# ROM-Adapter5.net
KiCad netlist of a schematic drawn in EAGLE
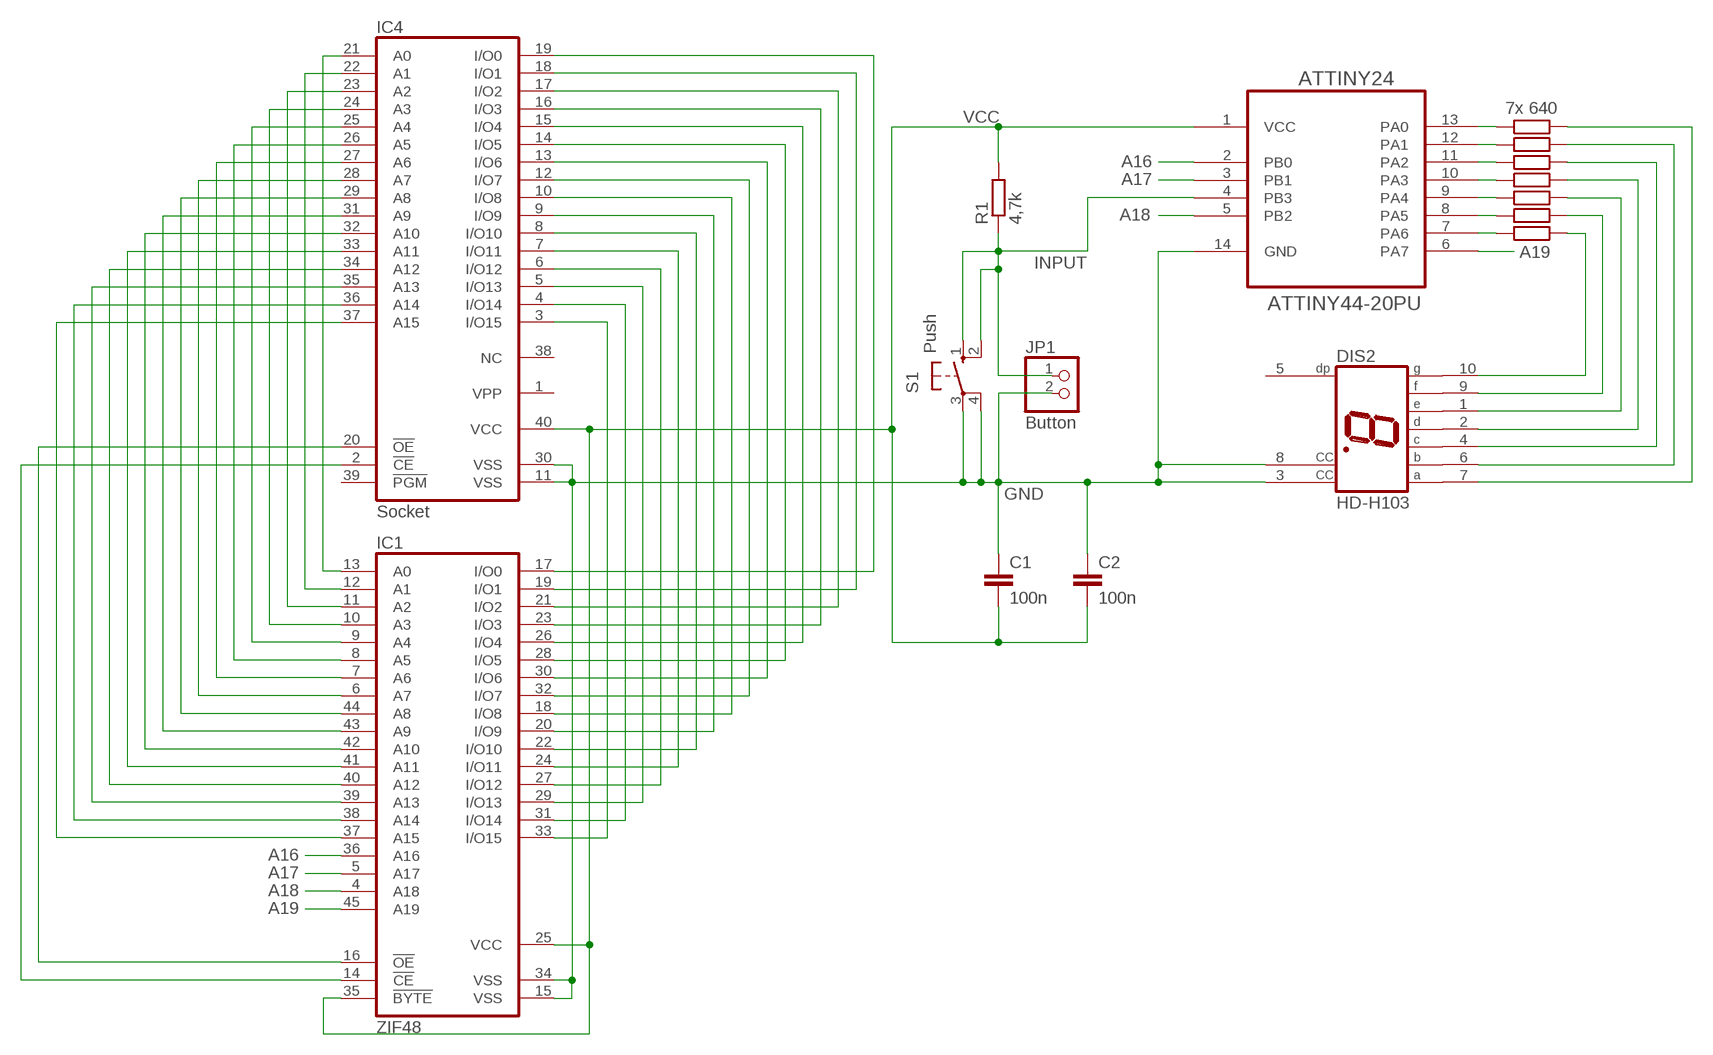
[diagram p0: schematic, sheet 1]

(export (version "E")
  (design (tool "Eeschema 10.0.6"))
  (components
    (comp (ref "ATTINY24")
      (value "ATTINY44-20PU")
      (footprint "eagle-import:DIP254P762X533-14")
      (libsource (lib "eagle-import") (part "ATTINY44-20PU"))
    )
    (comp (ref "C1")
      (value "100n")
      (footprint "eagle-import:C025-030X050")
      (libsource (lib "eagle-import") (part "C-EU025-030X050"))
    )
    (comp (ref "C2")
      (value "100n")
      (footprint "eagle-import:C025-030X050")
      (libsource (lib "eagle-import") (part "C-EU025-030X050"))
    )
    (comp (ref "DIS2")
      (value "HD-H103")
      (footprint "eagle-import:HDSP-M")
      (libsource (lib "eagle-import") (part "HD-H103"))
    )
    (comp (ref "IC1")
      (value "ZIF48")
      (footprint "eagle-import:MEMORY-HITACHI_ZIF48")
      (libsource (lib "eagle-import") (part "MEMORY-M27C160"))
    )
    (comp (ref "IC4")
      (value "Socket")
      (footprint "eagle-import:DIL40")
      (libsource (lib "eagle-import") (part "27C1024HG"))
    )
    (comp (ref "JP1")
      (value "Button")
      (footprint "eagle-import:1X02")
      (libsource (lib "eagle-import") (part "PINHD-1X2"))
    )
    (comp (ref "R1")
      (value "4,7k")
      (footprint "eagle-import:0207_10")
      (libsource (lib "eagle-import") (part "R-EU_0207/10"))
    )
    (comp (ref "R2")
      (value "7x 640")
      (footprint "eagle-import:0207_10")
      (libsource (lib "eagle-import") (part "R-EU_0207/10"))
    )
    (comp (ref "R3")
      (value "640")
      (footprint "eagle-import:0207_10")
      (libsource (lib "eagle-import") (part "R-EU_0207/10"))
    )
    (comp (ref "R4")
      (value "640")
      (footprint "eagle-import:0207_10")
      (libsource (lib "eagle-import") (part "R-EU_0207/10"))
    )
    (comp (ref "R5")
      (value "640")
      (footprint "eagle-import:0207_10")
      (libsource (lib "eagle-import") (part "R-EU_0207/10"))
    )
    (comp (ref "R6")
      (value "640")
      (footprint "eagle-import:0207_10")
      (libsource (lib "eagle-import") (part "R-EU_0207/10"))
    )
    (comp (ref "R7")
      (value "640")
      (footprint "eagle-import:0207_10")
      (libsource (lib "eagle-import") (part "R-EU_0207/10"))
    )
    (comp (ref "R8")
      (value "640")
      (footprint "eagle-import:0207_10")
      (libsource (lib "eagle-import") (part "R-EU_0207/10"))
    )
    (comp (ref "S1")
      (value "Push")
      (footprint "eagle-import:B3F-10XX")
      (fields (field (name "MPN") "B3F-1000"))
      (libsource (lib "eagle-import") (part "10-XX"))
    )
  )
  (nets
    (net (code "1") (name "/A16") (class "Default")
      (node (ref "ATTINY24") (pin "2") (pinfunction "PB0_2") (pintype "bidirectional"))
      (node (ref "IC1") (pin "36") (pinfunction "A16_36") (pintype "input"))
    )
    (net (code "2") (name "/A17") (class "Default")
      (node (ref "ATTINY24") (pin "3") (pinfunction "PB1_3") (pintype "bidirectional"))
      (node (ref "IC1") (pin "5") (pinfunction "A17_5") (pintype "input"))
    )
    (net (code "3") (name "/A18") (class "Default")
      (node (ref "ATTINY24") (pin "5") (pinfunction "PB2_5") (pintype "bidirectional"))
      (node (ref "IC1") (pin "4") (pinfunction "A18_4") (pintype "input"))
    )
    (net (code "4") (name "/A19") (class "Default")
      (node (ref "ATTINY24") (pin "6") (pinfunction "PA7_6") (pintype "bidirectional"))
      (node (ref "IC1") (pin "45") (pinfunction "A19_45") (pintype "input"))
    )
    (net (code "5") (name "/GND") (class "Default")
      (node (ref "ATTINY24") (pin "14") (pinfunction "GND_14") (pintype "passive"))
      (node (ref "C1") (pin "1") (pinfunction "1_1") (pintype "passive"))
      (node (ref "C2") (pin "1") (pinfunction "1_1") (pintype "passive"))
      (node (ref "DIS2") (pin "3") (pinfunction "CC_3") (pintype "passive"))
      (node (ref "DIS2") (pin "8") (pinfunction "CC_8") (pintype "passive"))
      (node (ref "IC1") (pin "15") (pinfunction "VSS_15") (pintype "power_in"))
      (node (ref "IC1") (pin "34") (pinfunction "VSS_34") (pintype "power_in"))
      (node (ref "IC4") (pin "11") (pinfunction "VSS_11") (pintype "power_in"))
      (node (ref "IC4") (pin "30") (pinfunction "VSS_30") (pintype "power_in"))
      (node (ref "JP1") (pin "2") (pinfunction "2_2") (pintype "passive"))
      (node (ref "S1") (pin "3") (pinfunction "P_3") (pintype "passive"))
      (node (ref "S1") (pin "4") (pinfunction "P1_4") (pintype "passive"))
    )
    (net (code "6") (name "/INPUT") (class "Default")
      (node (ref "ATTINY24") (pin "4") (pinfunction "PB3_4") (pintype "bidirectional"))
      (node (ref "JP1") (pin "1") (pinfunction "1_1") (pintype "passive"))
      (node (ref "R1") (pin "1") (pinfunction "1_1") (pintype "passive"))
      (node (ref "S1") (pin "1") (pinfunction "S_1") (pintype "passive"))
      (node (ref "S1") (pin "2") (pinfunction "S1_2") (pintype "passive"))
    )
    (net (code "7") (name "/VCC") (class "Default")
      (node (ref "ATTINY24") (pin "1") (pinfunction "VCC_1") (pintype "power_in"))
      (node (ref "C1") (pin "2") (pinfunction "2_2") (pintype "passive"))
      (node (ref "C2") (pin "2") (pinfunction "2_2") (pintype "passive"))
      (node (ref "IC1") (pin "25") (pinfunction "VCC_25") (pintype "power_in"))
      (node (ref "IC1") (pin "35") (pinfunction "~{BYTE}_35") (pintype "input"))
      (node (ref "IC4") (pin "40") (pinfunction "VCC_40") (pintype "power_in"))
      (node (ref "R1") (pin "2") (pinfunction "2_2") (pintype "passive"))
    )
    (net (code "8") (name "Net-(ATTINY24-PA0)") (class "Default")
      (node (ref "ATTINY24") (pin "13") (pinfunction "PA0_13") (pintype "bidirectional"))
      (node (ref "R2") (pin "1") (pinfunction "1_1") (pintype "passive"))
    )
    (net (code "9") (name "Net-(ATTINY24-PA1)") (class "Default")
      (node (ref "ATTINY24") (pin "12") (pinfunction "PA1_12") (pintype "bidirectional"))
      (node (ref "R3") (pin "1") (pinfunction "1_1") (pintype "passive"))
    )
    (net (code "10") (name "Net-(ATTINY24-PA2)") (class "Default")
      (node (ref "ATTINY24") (pin "11") (pinfunction "PA2_11") (pintype "bidirectional"))
      (node (ref "R4") (pin "1") (pinfunction "1_1") (pintype "passive"))
    )
    (net (code "11") (name "Net-(ATTINY24-PA3)") (class "Default")
      (node (ref "ATTINY24") (pin "10") (pinfunction "PA3_10") (pintype "bidirectional"))
      (node (ref "R5") (pin "1") (pinfunction "1_1") (pintype "passive"))
    )
    (net (code "12") (name "Net-(ATTINY24-PA4)") (class "Default")
      (node (ref "ATTINY24") (pin "9") (pinfunction "PA4_9") (pintype "bidirectional"))
      (node (ref "R6") (pin "1") (pinfunction "1_1") (pintype "passive"))
    )
    (net (code "13") (name "Net-(ATTINY24-PA5)") (class "Default")
      (node (ref "ATTINY24") (pin "8") (pinfunction "PA5_8") (pintype "bidirectional"))
      (node (ref "R7") (pin "1") (pinfunction "1_1") (pintype "passive"))
    )
    (net (code "14") (name "Net-(ATTINY24-PA6)") (class "Default")
      (node (ref "ATTINY24") (pin "7") (pinfunction "PA6_7") (pintype "bidirectional"))
      (node (ref "R8") (pin "1") (pinfunction "1_1") (pintype "passive"))
    )
    (net (code "15") (name "Net-(DIS2-A)") (class "Default")
      (node (ref "DIS2") (pin "7") (pinfunction "A_7") (pintype "passive"))
      (node (ref "R2") (pin "2") (pinfunction "2_2") (pintype "passive"))
    )
    (net (code "16") (name "Net-(DIS2-B)") (class "Default")
      (node (ref "DIS2") (pin "6") (pinfunction "B_6") (pintype "passive"))
      (node (ref "R3") (pin "2") (pinfunction "2_2") (pintype "passive"))
    )
    (net (code "17") (name "Net-(DIS2-C)") (class "Default")
      (node (ref "DIS2") (pin "4") (pinfunction "C_4") (pintype "passive"))
      (node (ref "R4") (pin "2") (pinfunction "2_2") (pintype "passive"))
    )
    (net (code "18") (name "Net-(DIS2-D)") (class "Default")
      (node (ref "DIS2") (pin "2") (pinfunction "D_2") (pintype "passive"))
      (node (ref "R5") (pin "2") (pinfunction "2_2") (pintype "passive"))
    )
    (net (code "19") (name "Net-(DIS2-E)") (class "Default")
      (node (ref "DIS2") (pin "1") (pinfunction "E_1") (pintype "passive"))
      (node (ref "R6") (pin "2") (pinfunction "2_2") (pintype "passive"))
    )
    (net (code "20") (name "Net-(DIS2-F)") (class "Default")
      (node (ref "DIS2") (pin "9") (pinfunction "F_9") (pintype "passive"))
      (node (ref "R7") (pin "2") (pinfunction "2_2") (pintype "passive"))
    )
    (net (code "21") (name "Net-(DIS2-G)") (class "Default")
      (node (ref "DIS2") (pin "10") (pinfunction "G_10") (pintype "passive"))
      (node (ref "R8") (pin "2") (pinfunction "2_2") (pintype "passive"))
    )
    (net (code "22") (name "Net-(IC1-A0)") (class "Default")
      (node (ref "IC1") (pin "13") (pinfunction "A0_13") (pintype "input"))
      (node (ref "IC4") (pin "21") (pinfunction "A0_21") (pintype "input"))
    )
    (net (code "23") (name "Net-(IC1-A1)") (class "Default")
      (node (ref "IC1") (pin "12") (pinfunction "A1_12") (pintype "input"))
      (node (ref "IC4") (pin "22") (pinfunction "A1_22") (pintype "input"))
    )
    (net (code "24") (name "Net-(IC1-A2)") (class "Default")
      (node (ref "IC1") (pin "11") (pinfunction "A2_11") (pintype "input"))
      (node (ref "IC4") (pin "23") (pinfunction "A2_23") (pintype "input"))
    )
    (net (code "25") (name "Net-(IC1-A3)") (class "Default")
      (node (ref "IC1") (pin "10") (pinfunction "A3_10") (pintype "input"))
      (node (ref "IC4") (pin "24") (pinfunction "A3_24") (pintype "input"))
    )
    (net (code "26") (name "Net-(IC1-A4)") (class "Default")
      (node (ref "IC1") (pin "9") (pinfunction "A4_9") (pintype "input"))
      (node (ref "IC4") (pin "25") (pinfunction "A4_25") (pintype "input"))
    )
    (net (code "27") (name "Net-(IC1-A5)") (class "Default")
      (node (ref "IC1") (pin "8") (pinfunction "A5_8") (pintype "input"))
      (node (ref "IC4") (pin "26") (pinfunction "A5_26") (pintype "input"))
    )
    (net (code "28") (name "Net-(IC1-A6)") (class "Default")
      (node (ref "IC1") (pin "7") (pinfunction "A6_7") (pintype "input"))
      (node (ref "IC4") (pin "27") (pinfunction "A6_27") (pintype "input"))
    )
    (net (code "29") (name "Net-(IC1-A7)") (class "Default")
      (node (ref "IC1") (pin "6") (pinfunction "A7_6") (pintype "input"))
      (node (ref "IC4") (pin "28") (pinfunction "A7_28") (pintype "input"))
    )
    (net (code "30") (name "Net-(IC1-A8)") (class "Default")
      (node (ref "IC1") (pin "44") (pinfunction "A8_44") (pintype "input"))
      (node (ref "IC4") (pin "29") (pinfunction "A8_29") (pintype "input"))
    )
    (net (code "31") (name "Net-(IC1-A9)") (class "Default")
      (node (ref "IC1") (pin "43") (pinfunction "A9_43") (pintype "input"))
      (node (ref "IC4") (pin "31") (pinfunction "A9_31") (pintype "input"))
    )
    (net (code "32") (name "Net-(IC1-A10)") (class "Default")
      (node (ref "IC1") (pin "42") (pinfunction "A10_42") (pintype "input"))
      (node (ref "IC4") (pin "32") (pinfunction "A10_32") (pintype "input"))
    )
    (net (code "33") (name "Net-(IC1-A11)") (class "Default")
      (node (ref "IC1") (pin "41") (pinfunction "A11_41") (pintype "input"))
      (node (ref "IC4") (pin "33") (pinfunction "A11_33") (pintype "input"))
    )
    (net (code "34") (name "Net-(IC1-A12)") (class "Default")
      (node (ref "IC1") (pin "40") (pinfunction "A12_40") (pintype "input"))
      (node (ref "IC4") (pin "34") (pinfunction "A12_34") (pintype "input"))
    )
    (net (code "35") (name "Net-(IC1-A13)") (class "Default")
      (node (ref "IC1") (pin "39") (pinfunction "A13_39") (pintype "input"))
      (node (ref "IC4") (pin "35") (pinfunction "A13_35") (pintype "input"))
    )
    (net (code "36") (name "Net-(IC1-A14)") (class "Default")
      (node (ref "IC1") (pin "38") (pinfunction "A14_38") (pintype "input"))
      (node (ref "IC4") (pin "36") (pinfunction "A14_36") (pintype "input"))
    )
    (net (code "37") (name "Net-(IC1-A15)") (class "Default")
      (node (ref "IC1") (pin "37") (pinfunction "A15_37") (pintype "input"))
      (node (ref "IC4") (pin "37") (pinfunction "A15_37") (pintype "input"))
    )
    (net (code "38") (name "Net-(IC1-I{slash}O0)") (class "Default")
      (node (ref "IC1") (pin "17") (pinfunction "I/O0_17") (pintype "tri_state"))
      (node (ref "IC4") (pin "19") (pinfunction "I/O0_19") (pintype "tri_state"))
    )
    (net (code "39") (name "Net-(IC1-I{slash}O1)") (class "Default")
      (node (ref "IC1") (pin "19") (pinfunction "I/O1_19") (pintype "tri_state"))
      (node (ref "IC4") (pin "18") (pinfunction "I/O1_18") (pintype "tri_state"))
    )
    (net (code "40") (name "Net-(IC1-I{slash}O2)") (class "Default")
      (node (ref "IC1") (pin "21") (pinfunction "I/O2_21") (pintype "tri_state"))
      (node (ref "IC4") (pin "17") (pinfunction "I/O2_17") (pintype "tri_state"))
    )
    (net (code "41") (name "Net-(IC1-I{slash}O3)") (class "Default")
      (node (ref "IC1") (pin "23") (pinfunction "I/O3_23") (pintype "tri_state"))
      (node (ref "IC4") (pin "16") (pinfunction "I/O3_16") (pintype "tri_state"))
    )
    (net (code "42") (name "Net-(IC1-I{slash}O4)") (class "Default")
      (node (ref "IC1") (pin "26") (pinfunction "I/O4_26") (pintype "tri_state"))
      (node (ref "IC4") (pin "15") (pinfunction "I/O4_15") (pintype "tri_state"))
    )
    (net (code "43") (name "Net-(IC1-I{slash}O5)") (class "Default")
      (node (ref "IC1") (pin "28") (pinfunction "I/O5_28") (pintype "tri_state"))
      (node (ref "IC4") (pin "14") (pinfunction "I/O5_14") (pintype "tri_state"))
    )
    (net (code "44") (name "Net-(IC1-I{slash}O6)") (class "Default")
      (node (ref "IC1") (pin "30") (pinfunction "I/O6_30") (pintype "tri_state"))
      (node (ref "IC4") (pin "13") (pinfunction "I/O6_13") (pintype "tri_state"))
    )
    (net (code "45") (name "Net-(IC1-I{slash}O7)") (class "Default")
      (node (ref "IC1") (pin "32") (pinfunction "I/O7_32") (pintype "tri_state"))
      (node (ref "IC4") (pin "12") (pinfunction "I/O7_12") (pintype "tri_state"))
    )
    (net (code "46") (name "Net-(IC1-I{slash}O8)") (class "Default")
      (node (ref "IC1") (pin "18") (pinfunction "I/O8_18") (pintype "tri_state"))
      (node (ref "IC4") (pin "10") (pinfunction "I/O8_10") (pintype "tri_state"))
    )
    (net (code "47") (name "Net-(IC1-I{slash}O9)") (class "Default")
      (node (ref "IC1") (pin "20") (pinfunction "I/O9_20") (pintype "tri_state"))
      (node (ref "IC4") (pin "9") (pinfunction "I/O9_9") (pintype "tri_state"))
    )
    (net (code "48") (name "Net-(IC1-I{slash}O10)") (class "Default")
      (node (ref "IC1") (pin "22") (pinfunction "I/O10_22") (pintype "tri_state"))
      (node (ref "IC4") (pin "8") (pinfunction "I/O10_8") (pintype "tri_state"))
    )
    (net (code "49") (name "Net-(IC1-I{slash}O11)") (class "Default")
      (node (ref "IC1") (pin "24") (pinfunction "I/O11_24") (pintype "tri_state"))
      (node (ref "IC4") (pin "7") (pinfunction "I/O11_7") (pintype "tri_state"))
    )
    (net (code "50") (name "Net-(IC1-I{slash}O12)") (class "Default")
      (node (ref "IC1") (pin "27") (pinfunction "I/O12_27") (pintype "tri_state"))
      (node (ref "IC4") (pin "6") (pinfunction "I/O12_6") (pintype "tri_state"))
    )
    (net (code "51") (name "Net-(IC1-I{slash}O13)") (class "Default")
      (node (ref "IC1") (pin "29") (pinfunction "I/O13_29") (pintype "tri_state"))
      (node (ref "IC4") (pin "5") (pinfunction "I/O13_5") (pintype "tri_state"))
    )
    (net (code "52") (name "Net-(IC1-I{slash}O14)") (class "Default")
      (node (ref "IC1") (pin "31") (pinfunction "I/O14_31") (pintype "tri_state"))
      (node (ref "IC4") (pin "4") (pinfunction "I/O14_4") (pintype "tri_state"))
    )
    (net (code "53") (name "Net-(IC1-I{slash}O15)") (class "Default")
      (node (ref "IC1") (pin "33") (pinfunction "I/O15_33") (pintype "tri_state"))
      (node (ref "IC4") (pin "3") (pinfunction "I/O15_3") (pintype "tri_state"))
    )
    (net (code "54") (name "Net-(IC1-~{CE})") (class "Default")
      (node (ref "IC1") (pin "14") (pinfunction "~{CE}_14") (pintype "input"))
      (node (ref "IC4") (pin "2") (pinfunction "~{CE}_2") (pintype "input"))
    )
    (net (code "55") (name "Net-(IC1-~{OE})") (class "Default")
      (node (ref "IC1") (pin "16") (pinfunction "~{OE}_16") (pintype "input"))
      (node (ref "IC4") (pin "20") (pinfunction "~{OE}_20") (pintype "input"))
    )
    (net (code "56") (name "unconnected-(DIS2-DP-Pad5)") (class "Default")
      (node (ref "DIS2") (pin "5") (pinfunction "DP_5") (pintype "passive"))
    )
    (net (code "57") (name "unconnected-(IC4-NC-Pad38)") (class "Default")
      (node (ref "IC4") (pin "38") (pinfunction "NC_38") (pintype "no_connect"))
    )
    (net (code "58") (name "unconnected-(IC4-VPP-Pad1)") (class "Default")
      (node (ref "IC4") (pin "1") (pinfunction "VPP_1") (pintype "passive"))
    )
    (net (code "59") (name "unconnected-(IC4-~{PGM}-Pad39)") (class "Default")
      (node (ref "IC4") (pin "39") (pinfunction "~{PGM}_39") (pintype "input"))
    )
  )
)
